# hbridge.net
KiCad netlist of a schematic drawn in EAGLE
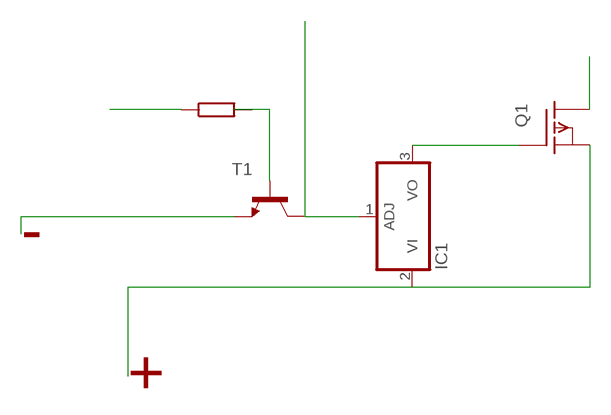
[diagram p0: schematic, sheet 1]

(export (version "E")
  (design (tool "Eeschema 10.0.6"))
  (components
    (comp (ref "IC1")
      (value "337T")
      (footprint "eagle-import:TO220H")
      (libsource (lib "eagle-import") (part "337T"))
    )
    (comp (ref "Q1")
      (value "IRF9530")
      (footprint "eagle-import:TO220")
      (libsource (lib "eagle-import") (part "IRF9530"))
    )
    (comp (ref "T1")
      (value "2N2222")
      (footprint "eagle-import:TO18")
      (libsource (lib "eagle-import") (part "2N2222"))
    )
  )
  (nets
    (net (code "1") (name "Net-(IC1-ADJ)") (class "Default")
      (node (ref "IC1") (pin "1") (pinfunction "ADJ_1") (pintype "input"))
      (node (ref "T1") (pin "3") (pinfunction "C_3") (pintype "passive"))
    )
    (net (code "2") (name "Net-(IC1-VI)") (class "Default")
      (node (ref "IC1") (pin "2") (pinfunction "VI_2") (pintype "input"))
      (node (ref "Q1") (pin "3") (pinfunction "S_3") (pintype "passive"))
    )
    (net (code "3") (name "Net-(IC1-VO)") (class "Default")
      (node (ref "IC1") (pin "3") (pinfunction "VO_3") (pintype "passive"))
      (node (ref "Q1") (pin "1") (pinfunction "G_1") (pintype "passive"))
    )
    (net (code "4") (name "unconnected-(Q1-D-Pad2)") (class "Default")
      (node (ref "Q1") (pin "2") (pinfunction "D_2") (pintype "passive"))
    )
    (net (code "5") (name "unconnected-(T1-B-Pad2)") (class "Default")
      (node (ref "T1") (pin "2") (pinfunction "B_2") (pintype "passive"))
    )
    (net (code "6") (name "unconnected-(T1-E-Pad1)") (class "Default")
      (node (ref "T1") (pin "1") (pinfunction "E_1") (pintype "passive"))
    )
  )
)
